# Indication.net
KiCad netlist of a schematic drawn in Altium Designer
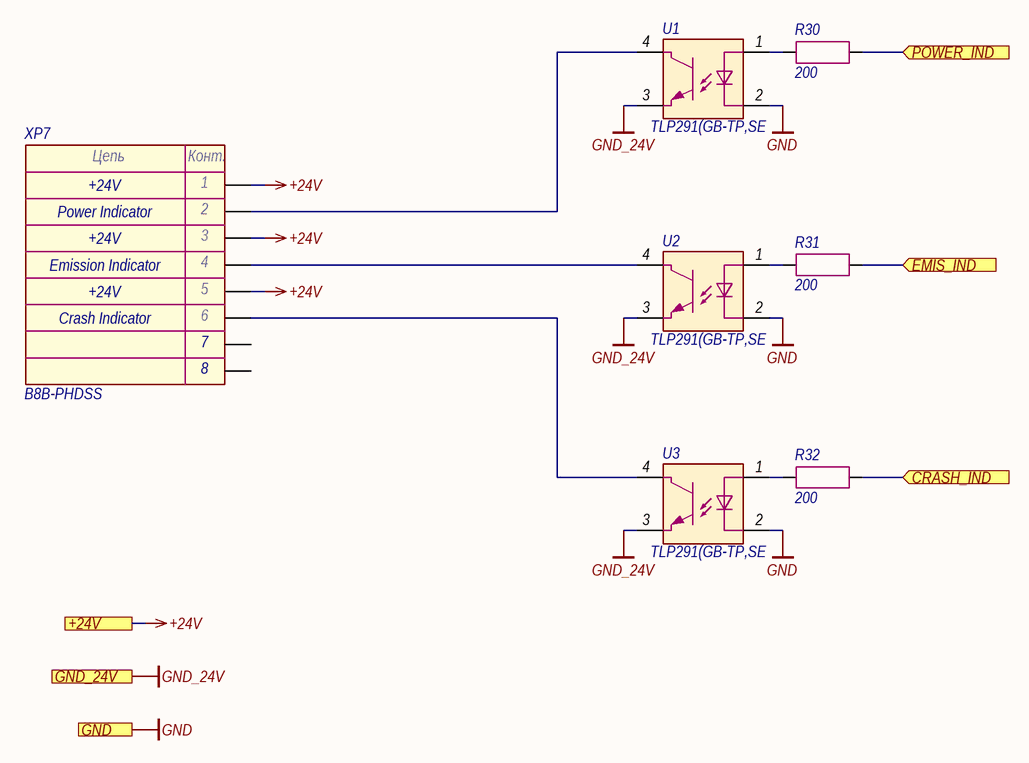
[diagram p0: Indication.SchDoc]

(export (version "E")
  (design (tool "Eeschema 10.0.6"))
  (components
    (comp (ref "R30")
      (value "200")
      (footprint "Pcb_library:RES_0603")
      (fields (field (name "MANUFACTURER") "Yageo"))
      (libsource (lib "Schem_library") (part "Resistor"))
    )
    (comp (ref "R31")
      (value "200")
      (footprint "Pcb_library:RES_0603")
      (fields (field (name "MANUFACTURER") "Yageo"))
      (libsource (lib "Schem_library") (part "Resistor"))
    )
    (comp (ref "R32")
      (value "200")
      (footprint "Pcb_library:RES_0603")
      (fields (field (name "MANUFACTURER") "Yageo"))
      (libsource (lib "Schem_library") (part "Resistor"))
    )
    (comp (ref "U1")
      (value "TLP291(GB-TP,SE")
      (footprint "Pcb_library:11-3C1")
      (fields (field (name "MANUFACTURER") "Toshiba"))
      (libsource (lib "Schem_library") (part "TLP291"))
    )
    (comp (ref "U2")
      (value "TLP291(GB-TP,SE")
      (footprint "Pcb_library:11-3C1")
      (fields (field (name "MANUFACTURER") "Toshiba"))
      (libsource (lib "Schem_library") (part "TLP291"))
    )
    (comp (ref "U3")
      (value "TLP291(GB-TP,SE")
      (footprint "Pcb_library:11-3C1")
      (fields (field (name "MANUFACTURER") "Toshiba"))
      (libsource (lib "Schem_library") (part "TLP291"))
    )
    (comp (ref "XP7")
      (value "B8B-PHDSS")
      (footprint "Pcb_library:B8B-PHDSS")
      (fields (field (name "MANUFACTURER") "JST"))
      (libsource (lib "Schem_library") (part "Connector-8"))
    )
  )
  (nets
    (net (code "1") (name "+24V") (class "Default")
      (node (ref "XP7") (pin "1") (pintype "passive"))
      (node (ref "XP7") (pin "3") (pintype "passive"))
      (node (ref "XP7") (pin "5") (pintype "passive"))
    )
    (net (code "2") (name "/CRASH_IND") (class "Default")
      (node (ref "R32") (pin "2") (pinfunction "2_2") (pintype "passive"))
    )
    (net (code "3") (name "/EMIS_IND") (class "Default")
      (node (ref "R31") (pin "2") (pinfunction "2_2") (pintype "passive"))
    )
    (net (code "4") (name "/POWER_IND") (class "Default")
      (node (ref "R30") (pin "2") (pinfunction "2_2") (pintype "passive"))
    )
    (net (code "5") (name "GND") (class "Default")
      (node (ref "U1") (pin "2") (pintype "passive"))
      (node (ref "U2") (pin "2") (pintype "passive"))
      (node (ref "U3") (pin "2") (pintype "passive"))
    )
    (net (code "6") (name "GND_24V") (class "Default")
      (node (ref "U1") (pin "3") (pintype "passive"))
      (node (ref "U2") (pin "3") (pintype "passive"))
      (node (ref "U3") (pin "3") (pintype "passive"))
    )
    (net (code "7") (name "Net-(R30-Pad1)") (class "Default")
      (node (ref "R30") (pin "1") (pinfunction "1_1") (pintype "passive"))
      (node (ref "U1") (pin "1") (pintype "passive"))
    )
    (net (code "8") (name "Net-(R31-Pad1)") (class "Default")
      (node (ref "R31") (pin "1") (pinfunction "1_1") (pintype "passive"))
      (node (ref "U2") (pin "1") (pintype "passive"))
    )
    (net (code "9") (name "Net-(R32-Pad1)") (class "Default")
      (node (ref "R32") (pin "1") (pinfunction "1_1") (pintype "passive"))
      (node (ref "U3") (pin "1") (pintype "passive"))
    )
    (net (code "10") (name "Net-(U1-Pad4)") (class "Default")
      (node (ref "U1") (pin "4") (pintype "passive"))
      (node (ref "XP7") (pin "2") (pintype "passive"))
    )
    (net (code "11") (name "Net-(U2-Pad4)") (class "Default")
      (node (ref "U2") (pin "4") (pintype "passive"))
      (node (ref "XP7") (pin "4") (pintype "passive"))
    )
    (net (code "12") (name "Net-(U3-Pad4)") (class "Default")
      (node (ref "U3") (pin "4") (pintype "passive"))
      (node (ref "XP7") (pin "6") (pintype "passive"))
    )
    (net (code "13") (name "unconnected-(XP7-Pad7)") (class "Default")
      (node (ref "XP7") (pin "7") (pintype "passive"))
    )
    (net (code "14") (name "unconnected-(XP7-Pad8)") (class "Default")
      (node (ref "XP7") (pin "8") (pintype "passive"))
    )
  )
)
